# USB_Control_Unit.net
KiCad netlist of a schematic drawn in Altium Designer
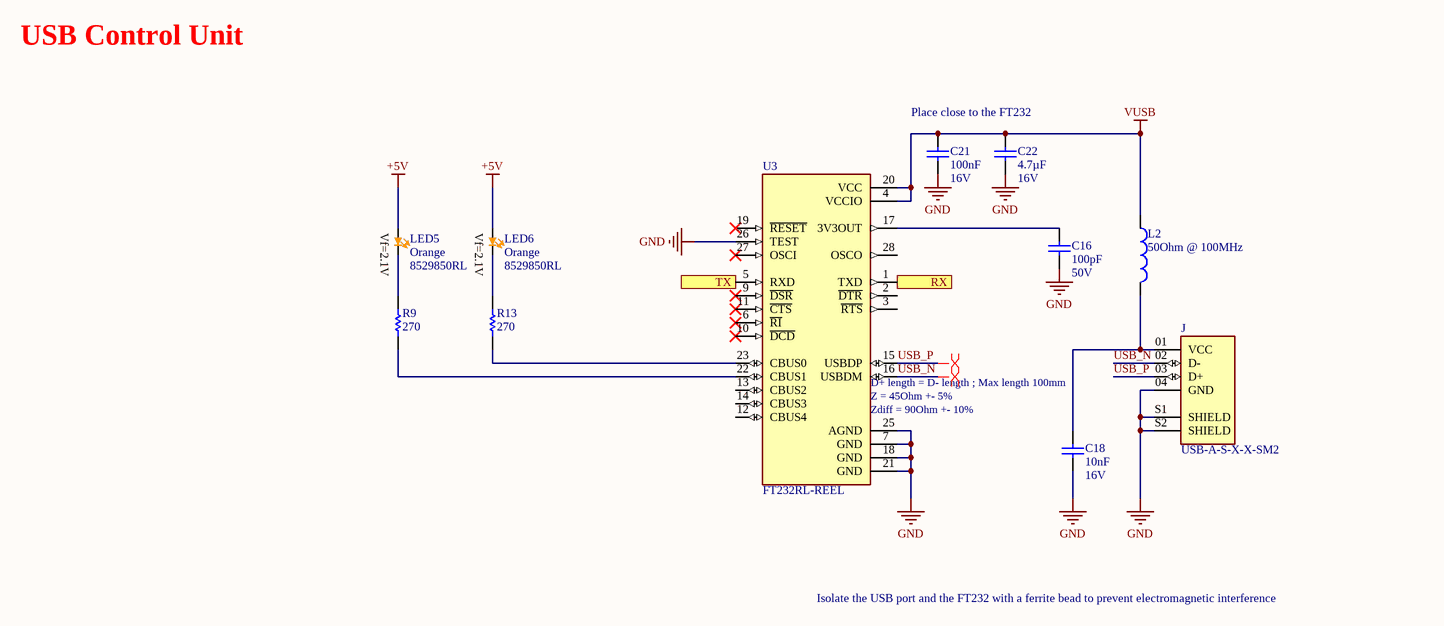
[diagram p0: USB Control Unit.SchDoc]

(export (version "E")
  (design (tool "Eeschema 10.0.6"))
  (components
    (comp (ref "C16")
      (value "100pF")
      (footprint "CC0201 x 0.33mm")
      (description "100pF ±2% 50V Ceramic Capacitor C0G, NP0 0201 (0603 Metric)")
      (fields
        (field (name "MANUFACTURER") "Murata Electronics")
        (field (name "PART NUMBER") "GRM0335C1H101GA01D")
        (field (name "VOLTAGE - RATED") "50V")
      )
      (libsource (lib "MLCC") (part "CAP"))
    )
    (comp (ref "C18")
      (value "10nF")
      (footprint "CC0603 x 0.95mm")
      (description "10000pF ±10% 16V Ceramic Capacitor X7R 0603 (1608 Metric)")
      (fields
        (field (name "MANUFACTURER") "Yageo")
        (field (name "PART NUMBER") "CS0603KRX7R7BB103")
        (field (name "VOLTAGE - RATED") "16V")
      )
      (libsource (lib "MLCC") (part "CAP"))
    )
    (comp (ref "C21")
      (value "100nF")
      (footprint "CC0603 x 0.90mm")
      (description "0.1µF ±10% 16V Ceramic Capacitor X7R 0603 (1608 Metric)")
      (fields
        (field (name "MANUFACTURER") "Yageo")
        (field (name "PART NUMBER") "CC0603KRX7R7BB104")
        (field (name "VOLTAGE - RATED") "16V")
      )
      (libsource (lib "MLCC") (part "CAP"))
    )
    (comp (ref "C22")
      (value "4.7µF")
      (footprint "CAP-SMT:CC0603 x 0.95mm")
      (description "4.7µF ±10% 16V Ceramic Capacitor X5R 0603 (1608 Metric)")
      (fields
        (field (name "MANUFACTURER") "Yageo")
        (field (name "PART NUMBER") "CC0603KRX5R7BB475")
        (field (name "VOLTAGE - RATED") "16V")
      )
      (libsource (lib "MLCC") (part "CAP"))
    )
    (comp (ref "J")
      (value "USB-A-S-X-X-SM2")
      (footprint "SAMTEC_USB-A-S-X-X-SM2")
      (description "USB-A (USB TYPE-A) USB 2.0 Receptacle Connector 4 Position Surface Mount, Right Angle")
      (fields (field (name "MP") "USB-A-S-F-B-SM2") (field (name "MF") "Samtec"))
      (libsource (lib "USB-A-S-X-X-SM2") (part "USB-A-S-X-X-SM2"))
    )
    (comp (ref "L2")
      (value "50Ohm @ 100MHz")
      (footprint "MMZ1608D500CTDH5")
      (libsource (lib "MMZ1608D500CTDH5") (part "MMZ1608D500CTDH5"))
    )
    (comp (ref "LED5")
      (value "Orange")
      (footprint "LED 0603 ORANGE")
      (description "1.6 mm x 0.8 mm Orange SMD Top LED")
      (fields
        (field (name "AVNET PART NUMBER") "KINKPG1608SEKCT")
        (field (name "MANUFACTURER") "Kingbright")
        (field (name "SUPPLIER PART NUMBER 1") "8529850RL")
      )
      (libsource (lib "Kingbright") (part "KP-1608SECK"))
    )
    (comp (ref "LED6")
      (value "Orange")
      (footprint "LED 0603 ORANGE")
      (description "1.6 mm x 0.8 mm Orange SMD Top LED")
      (fields
        (field (name "AVNET PART NUMBER") "KINKPG1608SEKCT")
        (field (name "MANUFACTURER") "Kingbright")
        (field (name "SUPPLIER PART NUMBER 1") "8529850RL")
      )
      (libsource (lib "Kingbright") (part "KP-1608SECK"))
    )
    (comp (ref "R9")
      (value "270")
      (footprint "RESC0603_N")
      (description "RES 270 OHM 1/10W .1% SMD 0603")
      (fields (field (name "PART NUMBER") "RT0603BRE07270RL") (field (name "MANUFACTURER") "Yageo"))
      (libsource (lib "RES-SMT") (part "RES"))
    )
    (comp (ref "R13")
      (value "270")
      (footprint "RESC0603_N")
      (description "RES 270 OHM 1/10W .1% SMD 0603")
      (fields (field (name "PART NUMBER") "RT0603BRE07270RL") (field (name "MANUFACTURER") "Yageo"))
      (libsource (lib "RES-SMT") (part "RES"))
    )
    (comp (ref "U3")
      (value "FT232RL-REEL")
      (footprint "SOP65P780X200-28N")
      (description "USB Bridge, USB to UART USB 2.0 UART Interface 28-SSOP")
      (fields (field (name "MF") "FTDI,") (field (name "DIGI-KEY_PART_NUMBER") "768-1007-1-ND"))
      (libsource (lib "FT232RL-REEL") (part "FT232RL-REEL"))
    )
  )
  (nets
    (net (code "1") (name "+5V") (class "Default")
      (node (ref "LED5") (pin "2") (pinfunction "A_2") (pintype "passive"))
      (node (ref "LED6") (pin "2") (pinfunction "A_2") (pintype "passive"))
    )
    (net (code "2") (name "/RX") (class "Default")
      (node (ref "U3") (pin "1") (pinfunction "TXD_1") (pintype "output"))
    )
    (net (code "3") (name "/TX") (class "Default")
      (node (ref "U3") (pin "5") (pinfunction "RXD_5") (pintype "input"))
    )
    (net (code "4") (name "/USB_N") (class "Default")
      (node (ref "J") (pin "02") (pinfunction "D-_02") (pintype "bidirectional"))
      (node (ref "U3") (pin "16") (pinfunction "USBDM_16") (pintype "bidirectional"))
    )
    (net (code "5") (name "/USB_P") (class "Default")
      (node (ref "J") (pin "03") (pinfunction "D+_03") (pintype "bidirectional"))
      (node (ref "U3") (pin "15") (pinfunction "USBDP_15") (pintype "bidirectional"))
    )
    (net (code "6") (name "GND") (class "Default")
      (node (ref "C16") (pin "1") (pinfunction "1_1") (pintype "passive"))
      (node (ref "C18") (pin "1") (pinfunction "1_1") (pintype "passive"))
      (node (ref "C21") (pin "1") (pinfunction "1_1") (pintype "passive"))
      (node (ref "C22") (pin "1") (pinfunction "1_1") (pintype "passive"))
      (node (ref "J") (pin "04") (pinfunction "GND_04") (pintype "power_in"))
      (node (ref "J") (pin "S1") (pinfunction "SHIELD_S1") (pintype "passive"))
      (node (ref "J") (pin "S2") (pinfunction "SHIELD_S2") (pintype "passive"))
      (node (ref "U3") (pin "18") (pinfunction "GND_18") (pintype "power_in"))
      (node (ref "U3") (pin "21") (pinfunction "GND_21") (pintype "power_in"))
      (node (ref "U3") (pin "25") (pinfunction "AGND_25") (pintype "power_in"))
      (node (ref "U3") (pin "26") (pinfunction "TEST_26") (pintype "input"))
      (node (ref "U3") (pin "7") (pinfunction "GND_7") (pintype "power_in"))
    )
    (net (code "7") (name "Net-(J-VCC)") (class "Default")
      (node (ref "C18") (pin "2") (pinfunction "2_2") (pintype "passive"))
      (node (ref "J") (pin "01") (pinfunction "VCC_01") (pintype "power_in"))
      (node (ref "L2") (pin "2") (pinfunction "2_2") (pintype "passive"))
    )
    (net (code "8") (name "Net-(LED5-K)") (class "Default")
      (node (ref "LED5") (pin "1") (pinfunction "K_1") (pintype "passive"))
      (node (ref "R9") (pin "2") (pinfunction "2_2") (pintype "passive"))
    )
    (net (code "9") (name "Net-(LED6-K)") (class "Default")
      (node (ref "LED6") (pin "1") (pinfunction "K_1") (pintype "passive"))
      (node (ref "R13") (pin "2") (pinfunction "2_2") (pintype "passive"))
    )
    (net (code "10") (name "Net-(U3-3V3OUT)") (class "Default")
      (node (ref "C16") (pin "2") (pinfunction "2_2") (pintype "passive"))
      (node (ref "U3") (pin "17") (pinfunction "3V3OUT_17") (pintype "output"))
    )
    (net (code "11") (name "Net-(U3-CBUS0)") (class "Default")
      (node (ref "R13") (pin "1") (pinfunction "1_1") (pintype "passive"))
      (node (ref "U3") (pin "23") (pinfunction "CBUS0_23") (pintype "bidirectional"))
    )
    (net (code "12") (name "Net-(U3-CBUS1)") (class "Default")
      (node (ref "R9") (pin "1") (pinfunction "1_1") (pintype "passive"))
      (node (ref "U3") (pin "22") (pinfunction "CBUS1_22") (pintype "bidirectional"))
    )
    (net (code "13") (name "VUSB") (class "Default")
      (node (ref "C21") (pin "2") (pinfunction "2_2") (pintype "passive"))
      (node (ref "C22") (pin "2") (pinfunction "2_2") (pintype "passive"))
      (node (ref "L2") (pin "1") (pinfunction "1_1") (pintype "passive"))
      (node (ref "U3") (pin "20") (pinfunction "VCC_20") (pintype "power_in"))
      (node (ref "U3") (pin "4") (pinfunction "VCCIO_4") (pintype "power_in"))
    )
    (net (code "14") (name "unconnected-(U3-CBUS2-Pad13)") (class "Default")
      (node (ref "U3") (pin "13") (pinfunction "CBUS2_13") (pintype "bidirectional"))
    )
    (net (code "15") (name "unconnected-(U3-CBUS3-Pad14)") (class "Default")
      (node (ref "U3") (pin "14") (pinfunction "CBUS3_14") (pintype "bidirectional"))
    )
    (net (code "16") (name "unconnected-(U3-CBUS4-Pad12)") (class "Default")
      (node (ref "U3") (pin "12") (pinfunction "CBUS4_12") (pintype "bidirectional"))
    )
    (net (code "17") (name "unconnected-(U3-OSCI-Pad27)") (class "Default")
      (node (ref "U3") (pin "27") (pinfunction "OSCI_27") (pintype "input+no_connect"))
    )
    (net (code "18") (name "unconnected-(U3-OSCO-Pad28)") (class "Default")
      (node (ref "U3") (pin "28") (pinfunction "OSCO_28") (pintype "output"))
    )
    (net (code "19") (name "unconnected-(U3-~{CTS}-Pad11)") (class "Default")
      (node (ref "U3") (pin "11") (pinfunction "~{CTS}_11") (pintype "input+no_connect"))
    )
    (net (code "20") (name "unconnected-(U3-~{DCD}-Pad10)") (class "Default")
      (node (ref "U3") (pin "10") (pinfunction "~{DCD}_10") (pintype "input+no_connect"))
    )
    (net (code "21") (name "unconnected-(U3-~{DSR}-Pad9)") (class "Default")
      (node (ref "U3") (pin "9") (pinfunction "~{DSR}_9") (pintype "input+no_connect"))
    )
    (net (code "22") (name "unconnected-(U3-~{DTR}-Pad2)") (class "Default")
      (node (ref "U3") (pin "2") (pinfunction "~{DTR}_2") (pintype "output"))
    )
    (net (code "23") (name "unconnected-(U3-~{RESET}-Pad19)") (class "Default")
      (node (ref "U3") (pin "19") (pinfunction "~{RESET}_19") (pintype "input+no_connect"))
    )
    (net (code "24") (name "unconnected-(U3-~{RI}-Pad6)") (class "Default")
      (node (ref "U3") (pin "6") (pinfunction "~{RI}_6") (pintype "input+no_connect"))
    )
    (net (code "25") (name "unconnected-(U3-~{RTS}-Pad3)") (class "Default")
      (node (ref "U3") (pin "3") (pinfunction "~{RTS}_3") (pintype "output"))
    )
  )
)
